# TSAL.net
KiCad netlist of a schematic drawn in Altium Designer
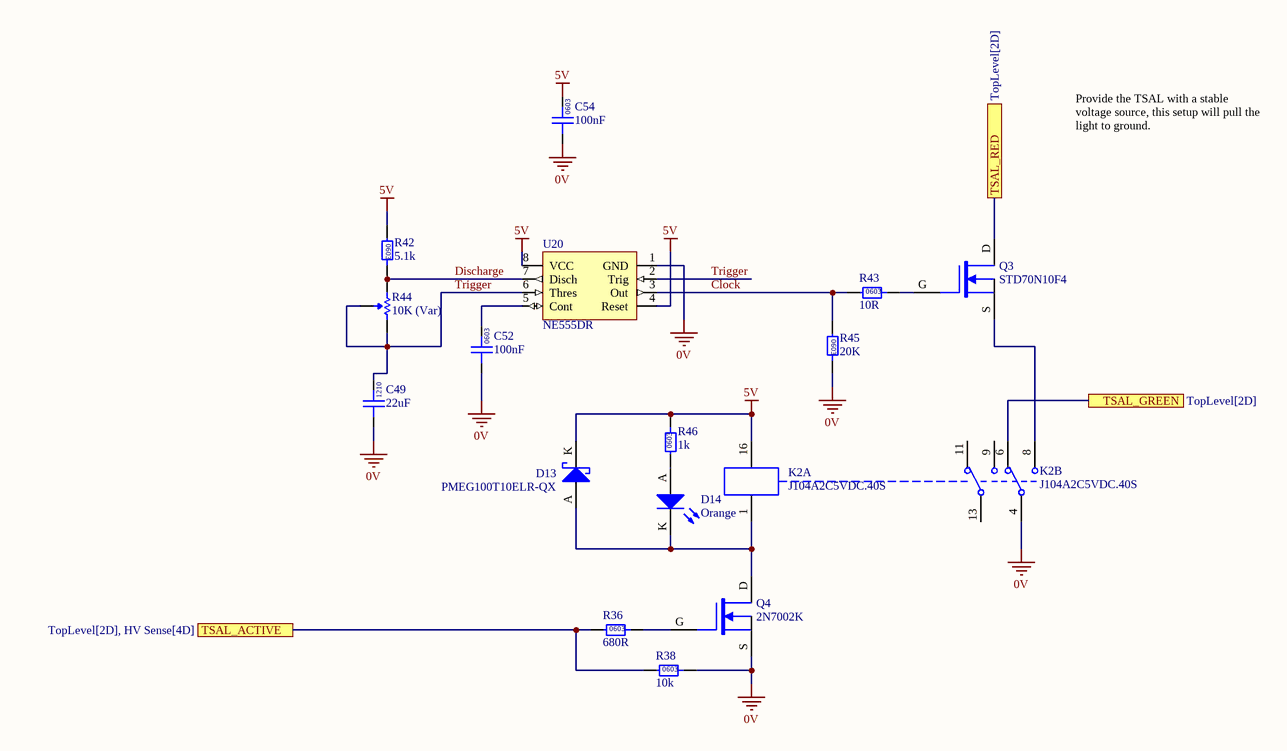
[diagram p0: TSAL.SchDoc]

(export (version "E")
  (design (tool "Eeschema 10.0.6"))
  (components
    (comp (ref "C49")
      (value "22uF")
      (footprint "1210")
      (fields
        (field (name "PART NUMBER") "GRM32ER71E226KE15L")
        (field (name "MANUFACTURER") "Murata Electronics")
        (field (name "TOLERANCE") "±10%")
      )
      (libsource (lib "ts_standard_library") (part "Capacitor 1210"))
    )
    (comp (ref "C52")
      (value "100nF")
      (footprint "0603")
      (fields
        (field (name "PART NUMBER") "GCM188L81H104KA57D")
        (field (name "MANUFACTURER") "muRata")
        (field (name "TOLERANCE") "±10%")
      )
      (libsource (lib "ts_standard_library") (part "Capacitor 0603"))
    )
    (comp (ref "C54")
      (value "100nF")
      (footprint "0603")
      (fields
        (field (name "PART NUMBER") "GCM188L81H104KA57D")
        (field (name "MANUFACTURER") "muRata")
        (field (name "TOLERANCE") "±10%")
      )
      (libsource (lib "ts_standard_library") (part "Capacitor 0603"))
    )
    (comp (ref "D13")
      (value "PMEG100T10ELR-QX")
      (footprint "NXP SOD123W")
      (fields
        (field (name "MANUFACTURER") "Nexperia USA Inc.")
        (field (name "DIGIKEY PART NUMBER") "1727-PMEG100T10ELR-QXCT-ND")
      )
      (libsource (lib "ts_standard_library") (part "Diode (Schottky)"))
    )
    (comp (ref "D14")
      (value "Orange")
      (footprint "0805 LED")
      (description "Orange LED Indication - Discrete 1.75V 0805 (2012 Metric)")
      (fields (field (name "PART NUMBER") "SML-211DTT86") (field (name "MANUFACTURER") "ROHM Semiconductor"))
      (libsource (lib "ts_standard_library") (part "LED"))
    )
    (comp (ref "K2")
      (value "J104A2C5VDC.40S")
      (footprint "J104A2C5VDC.40S-Footprint-1")
      (description "Relay Gen Purpose DPDT 3A 5V")
      (libsource (lib "") (part "J104A2C5VDC.40S_1"))
    )
    (comp (ref "Q3")
      (value "STD70N10F4")
      (footprint "STM TO-252 MOSFET")
      (description "N-Channel 100V 60A (Tc) 125W (Tc) Surface Mount DPAK")
      (fields
        (field (name "MANUFACTURER") "STMicroelectronics")
        (field (name "DIGIKEY PART NUMBER") "497-8806-2-ND")
        (field (name "PUBLISHER") "Altium Limited")
      )
      (libsource (lib "ts_standard_library") (part "MOSFET-N"))
    )
    (comp (ref "Q4")
      (value "2N7002K")
      (footprint "2N7002K-Footprint-1")
      (description "60V 380mA, NFET MOSTFET (Small Signal)")
      (libsource (lib "Team Swinburne") (part "2N7002K"))
    )
    (comp (ref "R36")
      (value "680R")
      (footprint "0603")
      (fields
        (field (name "PART NUMBER") "RC0603JR-13680RL")
        (field (name "MANUFACTURER") "YAGEO")
        (field (name "TOLERANCE") "0.01")
      )
      (libsource (lib "ts_standard_library") (part "Resistor 0603"))
    )
    (comp (ref "R38")
      (value "10k")
      (footprint "0603")
      (fields
        (field (name "PART NUMBER") "RC0603FR-0710KL")
        (field (name "MANUFACTURER") "YAGEO")
        (field (name "TOLERANCE") "0.01")
      )
      (libsource (lib "ts_standard_library") (part "Resistor 0603"))
    )
    (comp (ref "R42")
      (value "5.1k")
      (footprint "0603")
      (fields
        (field (name "PART NUMBER") "RC0603JR-075K1L")
        (field (name "MANUFACTURER") "YAGEO")
        (field (name "TOLERANCE") "0.01")
      )
      (libsource (lib "ts_standard_library") (part "Resistor 0603"))
    )
    (comp (ref "R43")
      (value "10R")
      (footprint "0603")
      (fields
        (field (name "PART NUMBER") "RC0603FR-0710RL")
        (field (name "MANUFACTURER") "YAGEO")
        (field (name "TOLERANCE") "0.01")
      )
      (libsource (lib "ts_standard_library") (part "Resistor 0603"))
    )
    (comp (ref "R44")
      (value "10K (Var)")
      (footprint "B 3296")
      (fields
        (field (name "PART NUMBER") "3296W-1-103LF")
        (field (name "MANUFACTURER") "Bournes Inc")
        (field (name "TOLERANCE") "0.1")
      )
      (libsource (lib "ts_standard_library") (part "Resistor (Potentiometer)"))
    )
    (comp (ref "R45")
      (value "20K")
      (footprint "0603")
      (fields
        (field (name "PART NUMBER") "RC0603FR-0720KL")
        (field (name "MANUFACTURER") "YAGEO")
        (field (name "TOLERANCE") "0.01")
      )
      (libsource (lib "ts_standard_library") (part "Resistor 0603"))
    )
    (comp (ref "R46")
      (value "1k")
      (footprint "0603")
      (fields
        (field (name "PART NUMBER") "RC0603FR-071KL")
        (field (name "MANUFACTURER") "YAGEO")
        (field (name "TOLERANCE") "0.01")
      )
      (libsource (lib "ts_standard_library") (part "Resistor 0603"))
    )
    (comp (ref "U20")
      (value "NE555DR")
      (footprint "TI 8-SOIC")
      (description "IC OSC SGL TIMER 100KHZ 8-SOIC")
      (libsource (lib "Team Swinburne") (part "NE555DR"))
    )
  )
  (nets
    (net (code "1") (name "/Clock") (class "Default")
      (node (ref "R43") (pin "1") (pinfunction "1_1") (pintype "passive"))
      (node (ref "R45") (pin "1") (pinfunction "1_1") (pintype "passive"))
      (node (ref "U20") (pin "3") (pinfunction "Out_3") (pintype "output"))
    )
    (net (code "2") (name "/Discharge") (class "Default")
      (node (ref "R42") (pin "2") (pinfunction "2_2") (pintype "passive"))
      (node (ref "R44") (pin "3") (pinfunction "CW_3") (pintype "passive"))
      (node (ref "U20") (pin "7") (pinfunction "Disch_7") (pintype "output"))
    )
    (net (code "3") (name "/TSAL_ACTIVE") (class "Default")
      (node (ref "R36") (pin "1") (pinfunction "1_1") (pintype "passive"))
      (node (ref "R38") (pin "1") (pinfunction "1_1") (pintype "passive"))
    )
    (net (code "4") (name "/TSAL_GREEN") (class "Default")
      (node (ref "K2") (pin "6") (pinfunction "6_6") (pintype "passive"))
    )
    (net (code "5") (name "/TSAL_RED") (class "Default")
      (node (ref "Q3") (pin "D") (pinfunction "D_D") (pintype "passive"))
    )
    (net (code "6") (name "/Trigger") (class "Default")
      (node (ref "C49") (pin "2") (pinfunction "2_2") (pintype "passive"))
      (node (ref "R44") (pin "1") (pinfunction "CCW_1") (pintype "passive"))
      (node (ref "R44") (pin "2") (pinfunction "Wiper_2") (pintype "passive"))
      (node (ref "U20") (pin "2") (pinfunction "Trig_2") (pintype "input"))
      (node (ref "U20") (pin "6") (pinfunction "Thres_6") (pintype "input"))
    )
    (net (code "7") (name "0V") (class "Default")
      (node (ref "C49") (pin "1") (pinfunction "1_1") (pintype "passive"))
      (node (ref "C52") (pin "1") (pinfunction "1_1") (pintype "passive"))
      (node (ref "C54") (pin "1") (pinfunction "1_1") (pintype "passive"))
      (node (ref "K2") (pin "4") (pinfunction "4_4") (pintype "passive"))
      (node (ref "Q4") (pin "S") (pinfunction "S_S") (pintype "passive"))
      (node (ref "R38") (pin "2") (pinfunction "2_2") (pintype "passive"))
      (node (ref "R45") (pin "2") (pinfunction "2_2") (pintype "passive"))
      (node (ref "U20") (pin "1") (pinfunction "GND_1") (pintype "power_in"))
    )
    (net (code "8") (name "5V") (class "Default")
      (node (ref "C54") (pin "2") (pinfunction "2_2") (pintype "passive"))
      (node (ref "D13") (pin "K") (pinfunction "K_K") (pintype "passive"))
      (node (ref "K2") (pin "16") (pinfunction "16_16") (pintype "passive"))
      (node (ref "R42") (pin "1") (pinfunction "1_1") (pintype "passive"))
      (node (ref "R46") (pin "2") (pinfunction "2_2") (pintype "passive"))
      (node (ref "U20") (pin "4") (pinfunction "Reset_4") (pintype "passive"))
      (node (ref "U20") (pin "8") (pinfunction "VCC_8") (pintype "passive"))
    )
    (net (code "9") (name "Net-(D13-PadA)") (class "Default")
      (node (ref "D13") (pin "A") (pinfunction "A_A") (pintype "passive"))
      (node (ref "D14") (pin "K") (pinfunction "K_K") (pintype "passive"))
      (node (ref "K2") (pin "1") (pinfunction "1_1") (pintype "passive"))
      (node (ref "Q4") (pin "D") (pinfunction "D_D") (pintype "passive"))
    )
    (net (code "10") (name "Net-(D14-PadA)") (class "Default")
      (node (ref "D14") (pin "A") (pinfunction "A_A") (pintype "passive"))
      (node (ref "R46") (pin "1") (pinfunction "1_1") (pintype "passive"))
    )
    (net (code "11") (name "Net-(K2-Pad8)") (class "Default")
      (node (ref "K2") (pin "8") (pinfunction "8_8") (pintype "passive"))
      (node (ref "Q3") (pin "S") (pinfunction "S_S") (pintype "passive"))
    )
    (net (code "12") (name "Net-(Q3-PadG)") (class "Default")
      (node (ref "Q3") (pin "G") (pinfunction "G_G") (pintype "passive"))
      (node (ref "R43") (pin "2") (pinfunction "2_2") (pintype "passive"))
    )
    (net (code "13") (name "Net-(Q4-PadG)") (class "Default")
      (node (ref "Q4") (pin "G") (pinfunction "G_G") (pintype "passive"))
      (node (ref "R36") (pin "2") (pinfunction "2_2") (pintype "passive"))
    )
    (net (code "14") (name "Net-(U20-Cont)") (class "Default")
      (node (ref "C52") (pin "2") (pinfunction "2_2") (pintype "passive"))
      (node (ref "U20") (pin "5") (pinfunction "Cont_5") (pintype "bidirectional"))
    )
    (net (code "15") (name "unconnected-(K2-Pad9)") (class "Default")
      (node (ref "K2") (pin "9") (pinfunction "9_9") (pintype "passive"))
    )
    (net (code "16") (name "unconnected-(K2-Pad11)") (class "Default")
      (node (ref "K2") (pin "11") (pinfunction "11_11") (pintype "passive"))
    )
    (net (code "17") (name "unconnected-(K2-Pad13)") (class "Default")
      (node (ref "K2") (pin "13") (pinfunction "13_13") (pintype "passive"))
    )
  )
)
